# Power.net
KiCad netlist of a schematic drawn in Altium Designer
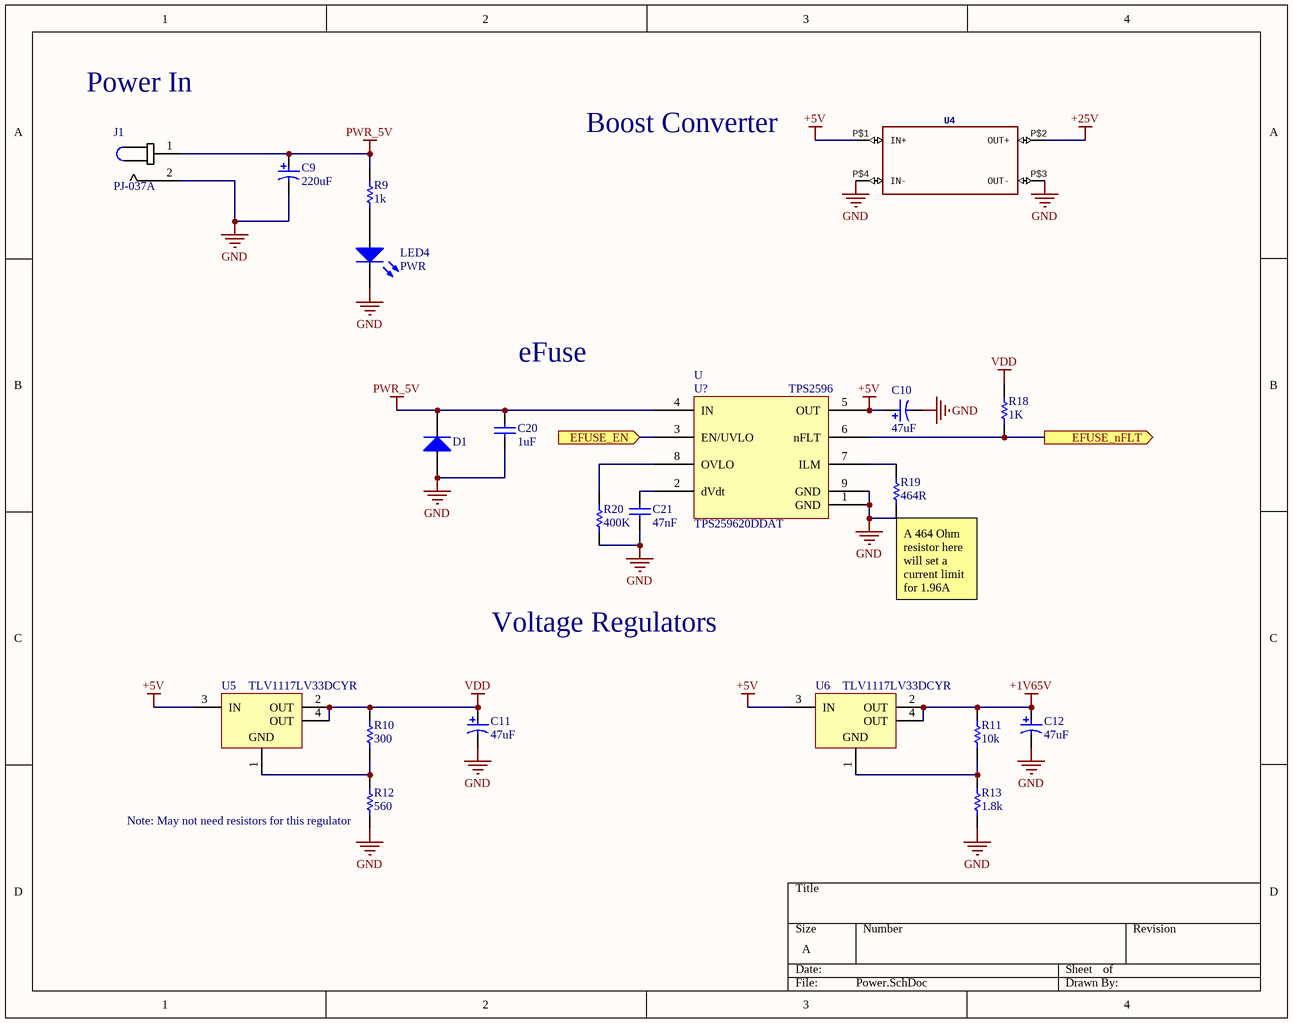
[diagram p0: Power.SchDoc]

(export (version "E")
  (design (tool "Eeschema 10.0.6"))
  (components
    (comp (ref "C9")
      (value "220uF")
      (footprint "PNSC-FP-V-F_V")
      (fields (field (name "MANUFACTURER") "Panasonic"))
      (libsource (lib "Altium Content Vault") (part "CAP-P-2"))
    )
    (comp (ref "C10")
      (value "47uF")
      (footprint "PNSC-FP-V-D_V")
      (fields (field (name "MANUFACTURER") "Panasonic"))
      (libsource (lib "Altium Content Vault") (part "CAP-P-2"))
    )
    (comp (ref "C11")
      (value "47uF")
      (footprint "PNSC-FP-V-D_V")
      (fields (field (name "MANUFACTURER") "Panasonic"))
      (libsource (lib "Altium Content Vault") (part "CAP-P-2"))
    )
    (comp (ref "C12")
      (value "47uF")
      (footprint "PNSC-FP-V-D_V")
      (fields (field (name "MANUFACTURER") "Panasonic"))
      (libsource (lib "Altium Content Vault") (part "CAP-P-2"))
    )
    (comp (ref "C20")
      (value "1uF")
      (footprint "CAPC1608X90X20LL10")
      (description "Chip Capacitor, 1 uF, +/- 10%, 50 V, -55 to 85 degC, 0603 (1608 Metric), RoHS, Tape and Reel")
      (fields
        (field (name "MANUFACTURER") "TDK")
        (field (name "PCN PART NUMBER") "MLCCPartNumberChange30/Nov/2012")
      )
      (libsource (lib "Altium Content Vault") (part "CAP-NP-2"))
    )
    (comp (ref "C21")
      (value "47nF")
      (footprint "CAPC1608X90X35ML10T15")
      (fields (field (name "MANUFACTURER") "Murata") (field (name "PART NUMBER") "GRM188R71H473KA61D"))
      (libsource (lib "Altium Content Vault") (part "CAP"))
    )
    (comp (ref "D1")
      (value "SMAJ5.0A-E3/61")
      (footprint "VISH-DO-214AC-2_M")
      (fields (field (name "MANUFACTURER") "Vishay Semiconductor"))
      (libsource (lib "Altium Content Vault") (part "VISH-K1A2-2"))
    )
    (comp (ref "J1")
      (value "PJ-037A")
      (footprint "*CUI_PJ-037A")
      (libsource (lib "PJ-037A") (part "PJ-037A"))
    )
    (comp (ref "LED4")
      (value "PWR")
      (footprint "0805_A")
      (description "SMD mono-color Chip LED, WL-SMCW, Super Red")
      (fields (field (name "MANUFACTURER") "Wuerth Elektronik") (field (name "PARTNUMBER") "150080SS75000"))
      (libsource (lib "Altium Content Vault") (part "WE-LED_K1A2-2"))
    )
    (comp (ref "R9")
      (value "1k")
      (footprint "RESC1608X55X30LL20T20")
      (fields (field (name "MANUFACTURER") "Panasonic") (field (name "PART NUMBER") "ERA3AEB102V"))
      (libsource (lib "Altium Content Vault") (part "RES"))
    )
    (comp (ref "R10")
      (value "300")
      (footprint "RESC1608X55X30LL15T15")
      (fields (field (name "MANUFACTURER") "Panasonic") (field (name "PART NUMBER") "ERJ-3EKF3000V"))
      (libsource (lib "Altium Content Vault") (part "RES"))
    )
    (comp (ref "R11")
      (value "10k")
      (footprint "RESC1608X55X30LL15T15")
      (fields (field (name "MANUFACTURER") "Panasonic") (field (name "PART NUMBER") "ERJ-3EKF3000V"))
      (libsource (lib "Altium Content Vault") (part "RES"))
    )
    (comp (ref "R12")
      (value "560")
      (footprint "RESC1608X55X30LL20T20")
      (fields (field (name "PART NUMBER") "ERA3AEB561V") (field (name "MANUFACTURER") "Panasonic"))
      (libsource (lib "Altium Content Vault") (part "RES"))
    )
    (comp (ref "R13")
      (value "1.8k")
      (footprint "RESC1609X50X30NL10T20")
      (fields (field (name "MANUFACTURER") "Vishay Dale") (field (name "PART NUMBER") "CRCW0603100RFKEA"))
      (libsource (lib "Altium Content Vault") (part "RES"))
    )
    (comp (ref "R18")
      (value "1K")
      (footprint "RESC1608X55X30LL15T15")
      (fields (field (name "MANUFACTURER") "Panasonic") (field (name "PART NUMBER") "ERJ-3EKF3000V"))
      (libsource (lib "Altium Content Vault") (part "RES"))
    )
    (comp (ref "R19")
      (value "464R")
      (footprint "RESC1608X55X30LL15T15")
      (fields (field (name "MANUFACTURER") "Panasonic") (field (name "PART NUMBER") "ERJ-3EKF3000V"))
      (libsource (lib "Altium Content Vault") (part "RES"))
    )
    (comp (ref "R20")
      (value "400K")
      (footprint "RESC1608X55X30LL15T15")
      (fields (field (name "MANUFACTURER") "Panasonic") (field (name "PART NUMBER") "ERJ-3EKF3000V"))
      (libsource (lib "Altium Content Vault") (part "RES"))
    )
    (comp (ref "U")
      (value "TPS259620DDAT")
      (footprint "TPS259620DDAT - duplicate")
      (description "Texas Instruments TPS259620DDAT")
      (libsource (lib "TI_TPS259620DDAT") (part "TI_TPS259620DDAT"))
    )
    (comp (ref "U4")
      (value "XL6009E1")
      (footprint "XL6009E1")
      (libsource (lib "VFD-Clock") (part "XL6009E1"))
    )
    (comp (ref "U5")
      (value "TLV1117LV33DCYR")
      (footprint "DCY0004A_M")
      (fields (field (name "MANUFACTURER") "Texas Instruments"))
      (libsource (lib "VFD_Clock_lib") (part "CMP-0395-00503-2"))
    )
    (comp (ref "U6")
      (value "TLV1117LV33DCYR")
      (footprint "DCY0004A_M")
      (fields (field (name "MANUFACTURER") "Texas Instruments"))
      (libsource (lib "VFD_Clock_lib") (part "CMP-0395-00503-2"))
    )
  )
  (nets
    (net (code "1") (name "+1V65V") (class "Default")
      (node (ref "C12") (pin "1") (pinfunction "1_1") (pintype "passive"))
      (node (ref "R11") (pin "2") (pinfunction "2_2") (pintype "passive"))
      (node (ref "U6") (pin "2") (pinfunction "OUT_2") (pintype "power_in"))
      (node (ref "U6") (pin "4") (pinfunction "OUT_4") (pintype "power_in"))
    )
    (net (code "2") (name "+5V") (class "Default")
      (node (ref "C10") (pin "1") (pinfunction "1_1") (pintype "passive"))
      (node (ref "U") (pin "5") (pinfunction "OUT_5") (pintype "passive"))
      (node (ref "U4") (pin "P$1") (pinfunction "IN+_P$1") (pintype "bidirectional"))
      (node (ref "U5") (pin "3") (pinfunction "IN_3") (pintype "power_in"))
      (node (ref "U6") (pin "3") (pinfunction "IN_3") (pintype "power_in"))
    )
    (net (code "3") (name "+25V") (class "Default")
      (node (ref "U4") (pin "P$2") (pinfunction "OUT+_P$2") (pintype "bidirectional"))
    )
    (net (code "4") (name "/EFUSE_EN") (class "Default")
      (node (ref "U") (pin "3") (pinfunction "EN/UVLO_3") (pintype "passive"))
    )
    (net (code "5") (name "/EFUSE_nFLT") (class "Default")
      (node (ref "R18") (pin "1") (pinfunction "1_1") (pintype "passive"))
      (node (ref "U") (pin "6") (pinfunction "nFLT_6") (pintype "passive"))
    )
    (net (code "6") (name "GND") (class "Default")
      (node (ref "C10") (pin "2") (pinfunction "2_2") (pintype "passive"))
      (node (ref "C11") (pin "2") (pinfunction "2_2") (pintype "passive"))
      (node (ref "C12") (pin "2") (pinfunction "2_2") (pintype "passive"))
      (node (ref "C20") (pin "1") (pinfunction "1_1") (pintype "passive"))
      (node (ref "C21") (pin "1") (pinfunction "1_1") (pintype "passive"))
      (node (ref "C9") (pin "2") (pinfunction "2_2") (pintype "passive"))
      (node (ref "D1") (pin "2") (pinfunction "A_2") (pintype "passive"))
      (node (ref "J1") (pin "2") (pinfunction "2_2") (pintype "passive"))
      (node (ref "LED4") (pin "1") (pinfunction "K_1") (pintype "passive"))
      (node (ref "R12") (pin "1") (pinfunction "1_1") (pintype "passive"))
      (node (ref "R13") (pin "2") (pinfunction "2_2") (pintype "passive"))
      (node (ref "R19") (pin "1") (pinfunction "1_1") (pintype "passive"))
      (node (ref "R20") (pin "1") (pinfunction "1_1") (pintype "passive"))
      (node (ref "U") (pin "1") (pinfunction "GND_1") (pintype "passive"))
      (node (ref "U") (pin "9") (pinfunction "GND_9") (pintype "passive"))
      (node (ref "U4") (pin "P$3") (pinfunction "OUT-_P$3") (pintype "bidirectional"))
      (node (ref "U4") (pin "P$4") (pinfunction "IN-_P$4") (pintype "bidirectional"))
    )
    (net (code "7") (name "Net-(LED4-A)") (class "Default")
      (node (ref "LED4") (pin "2") (pinfunction "A_2") (pintype "passive"))
      (node (ref "R9") (pin "1") (pinfunction "1_1") (pintype "passive"))
    )
    (net (code "8") (name "Net-(U-ILM)") (class "Default")
      (node (ref "R19") (pin "2") (pinfunction "2_2") (pintype "passive"))
      (node (ref "U") (pin "7") (pinfunction "ILM_7") (pintype "passive"))
    )
    (net (code "9") (name "Net-(U-OVLO)") (class "Default")
      (node (ref "R20") (pin "2") (pinfunction "2_2") (pintype "passive"))
      (node (ref "U") (pin "8") (pinfunction "OVLO_8") (pintype "passive"))
    )
    (net (code "10") (name "Net-(U-dVdt)") (class "Default")
      (node (ref "C21") (pin "2") (pinfunction "2_2") (pintype "passive"))
      (node (ref "U") (pin "2") (pinfunction "dVdt_2") (pintype "passive"))
    )
    (net (code "11") (name "Net-(U5-GND)") (class "Default")
      (node (ref "R10") (pin "1") (pinfunction "1_1") (pintype "passive"))
      (node (ref "R12") (pin "2") (pinfunction "2_2") (pintype "passive"))
      (node (ref "U5") (pin "1") (pinfunction "GND_1") (pintype "power_in"))
    )
    (net (code "12") (name "Net-(U6-GND)") (class "Default")
      (node (ref "R11") (pin "1") (pinfunction "1_1") (pintype "passive"))
      (node (ref "R13") (pin "1") (pinfunction "1_1") (pintype "passive"))
      (node (ref "U6") (pin "1") (pinfunction "GND_1") (pintype "power_in"))
    )
    (net (code "13") (name "PWR_5V") (class "Default")
      (node (ref "C20") (pin "2") (pinfunction "2_2") (pintype "passive"))
      (node (ref "C9") (pin "1") (pinfunction "1_1") (pintype "passive"))
      (node (ref "D1") (pin "1") (pinfunction "K_1") (pintype "passive"))
      (node (ref "J1") (pin "1") (pinfunction "1_1") (pintype "passive"))
      (node (ref "R9") (pin "2") (pinfunction "2_2") (pintype "passive"))
      (node (ref "U") (pin "4") (pinfunction "IN_4") (pintype "passive"))
    )
    (net (code "14") (name "VDD") (class "Default")
      (node (ref "C11") (pin "1") (pinfunction "1_1") (pintype "passive"))
      (node (ref "R10") (pin "2") (pinfunction "2_2") (pintype "passive"))
      (node (ref "R18") (pin "2") (pinfunction "2_2") (pintype "passive"))
      (node (ref "U5") (pin "2") (pinfunction "OUT_2") (pintype "power_in"))
      (node (ref "U5") (pin "4") (pinfunction "OUT_4") (pintype "power_in"))
    )
  )
)
